# secondary_LTC.net
KiCad netlist of a schematic drawn in Altium Designer
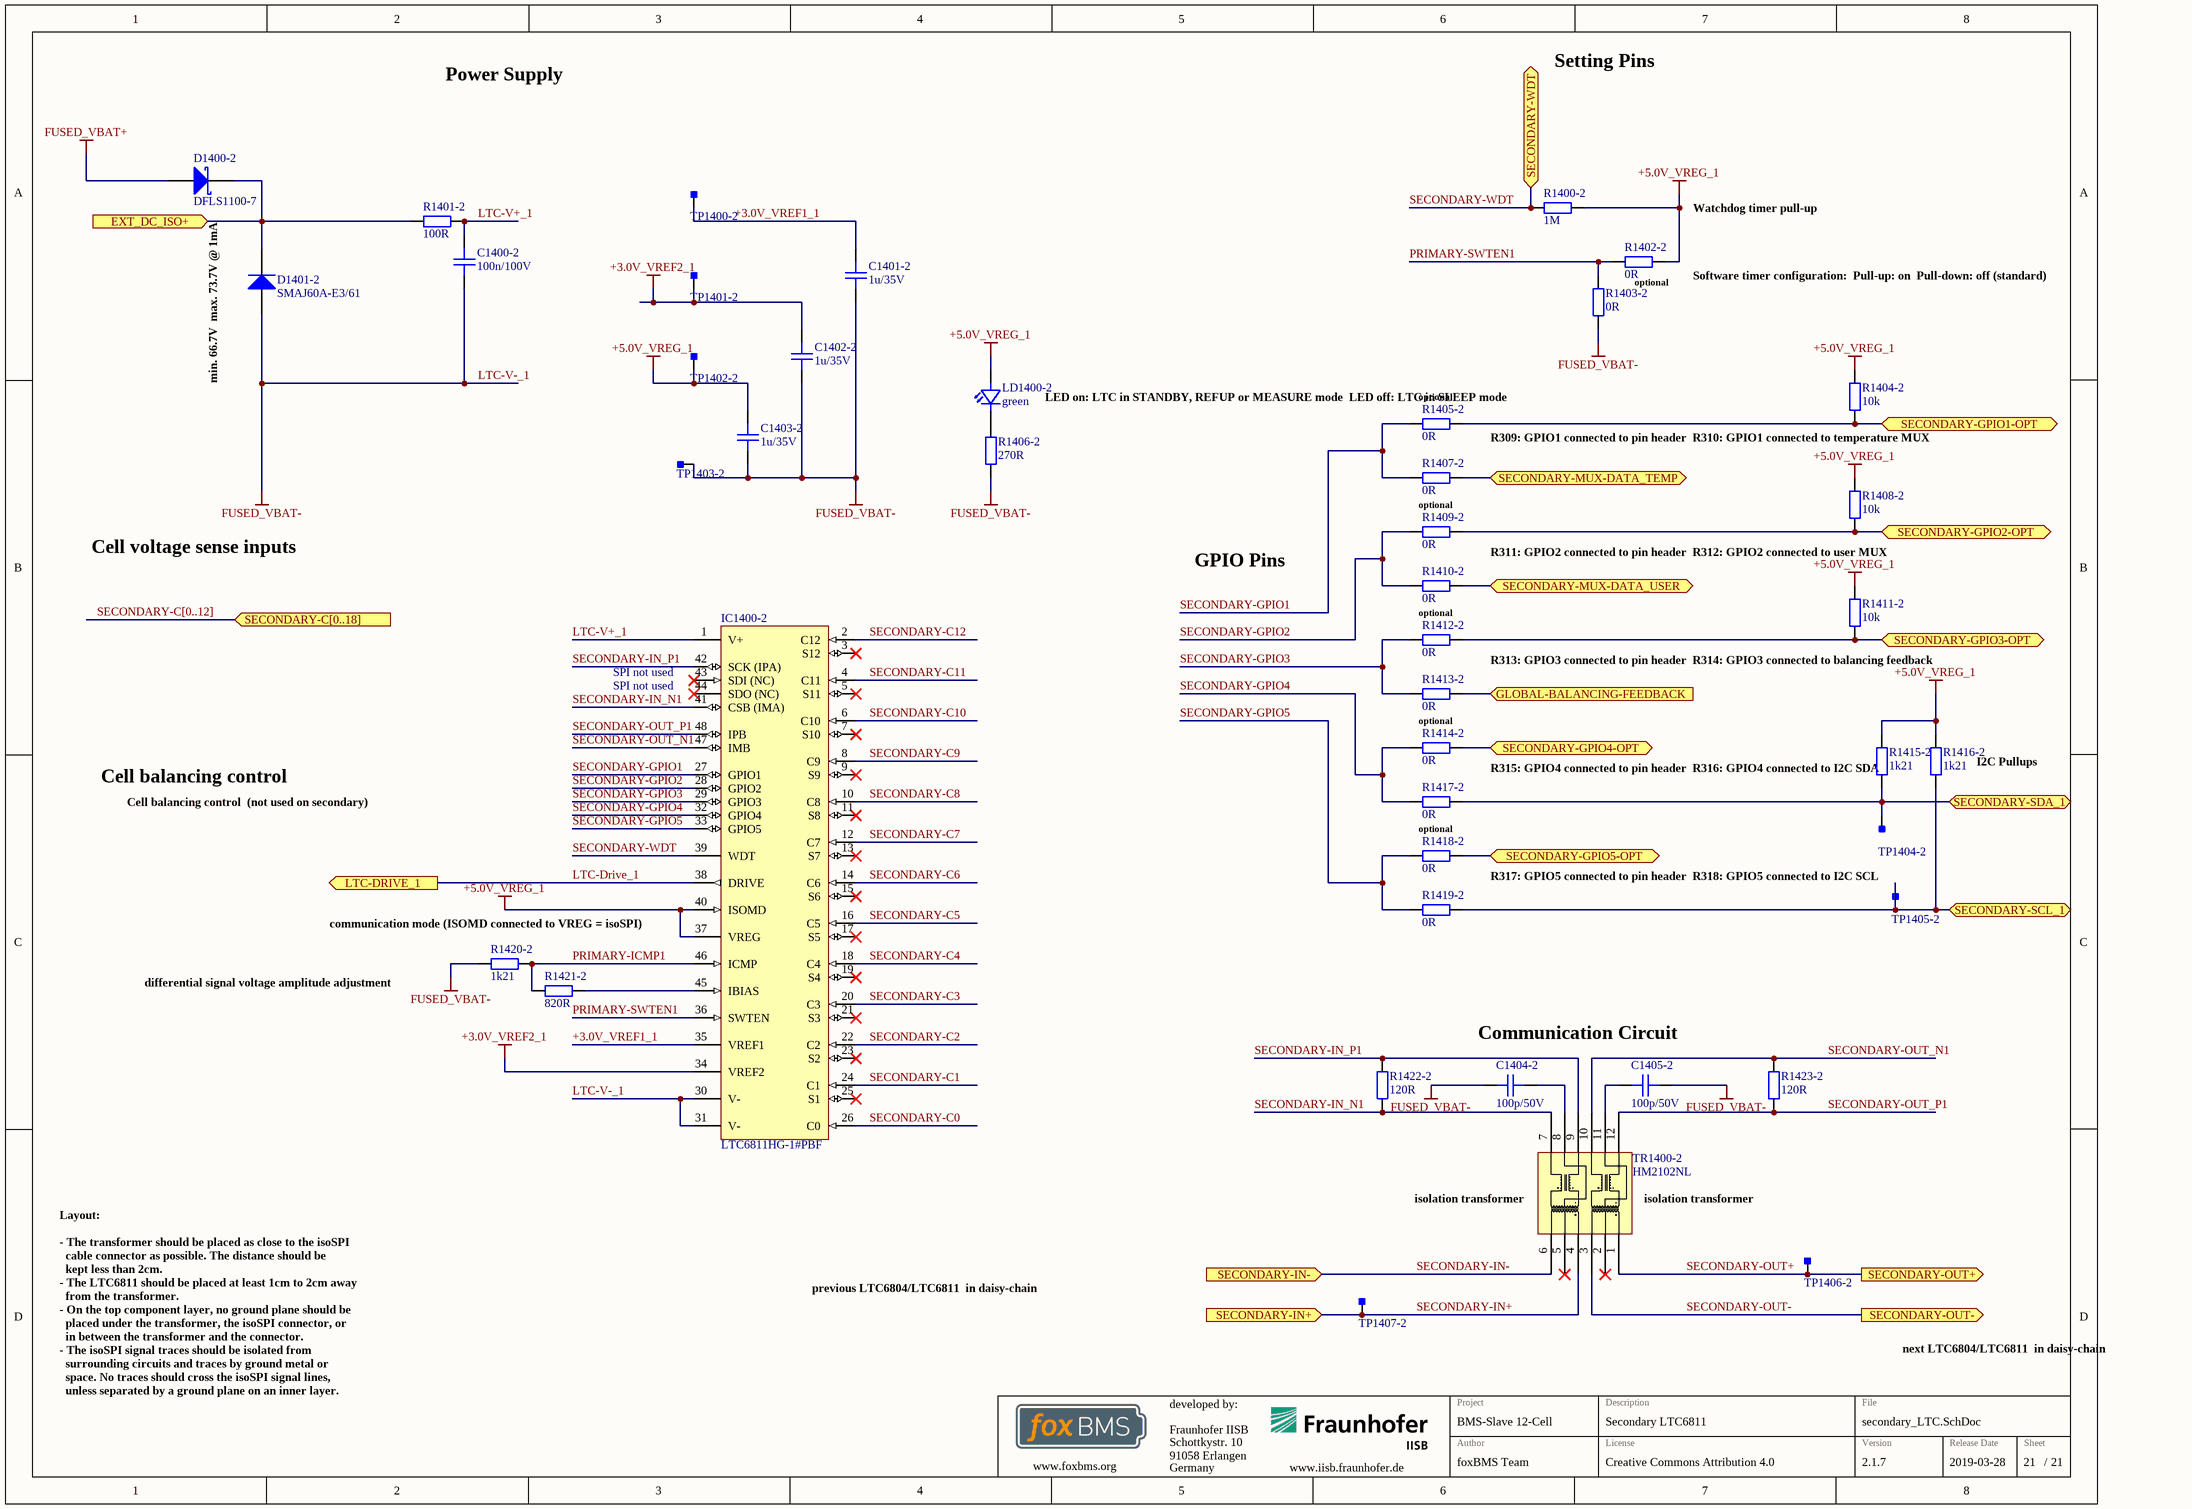
[diagram p0: secondary_LTC.SchDoc]

(export (version "E")
  (design (tool "Eeschema 10.0.6"))
  (components
    (comp (ref "C1400-2")
      (value "100n/100V")
      (footprint "CAPC2012X14N")
      (description "MLCC")
      (fields (field (name "PART NUMBER") "gen_C_ceramic_100n_100V_X7R_0805"))
      (libsource (lib "OE750") (part "C"))
    )
    (comp (ref "C1401-2")
      (value "1u/35V")
      (footprint "CAPC1608X08N")
      (description "MLCC")
      (fields (field (name "PART NUMBER") "gen_C_ceramic_1u_35V_X7R_0603"))
      (libsource (lib "OE750") (part "C"))
    )
    (comp (ref "C1402-2")
      (value "1u/35V")
      (footprint "CAPC1608X08N")
      (description "MLCC")
      (fields (field (name "PART NUMBER") "gen_C_ceramic_1u_35V_X7R_0603"))
      (libsource (lib "OE750") (part "C"))
    )
    (comp (ref "C1403-2")
      (value "1u/35V")
      (footprint "CAPC1608X08N")
      (description "MLCC")
      (fields (field (name "PART NUMBER") "gen_C_ceramic_1u_35V_X7R_0603"))
      (libsource (lib "OE750") (part "C"))
    )
    (comp (ref "C1404-2")
      (value "100p/50V")
      (footprint "CAPC1608X08N")
      (description "MLCC")
      (fields (field (name "PART NUMBER") "gen_C_ceramic_100p_50V_C0G_0603"))
      (libsource (lib "OE750") (part "C"))
    )
    (comp (ref "C1405-2")
      (value "100p/50V")
      (footprint "CAPC1608X08N")
      (description "MLCC")
      (fields (field (name "PART NUMBER") "gen_C_ceramic_100p_50V_C0G_0603"))
      (libsource (lib "OE750") (part "C"))
    )
    (comp (ref "D1400-2")
      (value "DFLS1100-7")
      (footprint "DIOD-POWERDI123-2_V")
      (fields (field (name "MANUFACTURER") "Diodes Inc"))
      (libsource (lib "Altium Content Vault") (part "DSKY-AK-2"))
    )
    (comp (ref "D1401-2")
      (value "SMAJ60A-E3/61")
      (footprint "VISH-DO-214AC-2_N")
      (fields (field (name "MANUFACTURER") "Vishay Semiconductor"))
      (libsource (lib "Altium Content Vault") (part "VISH-K1A2-2"))
    )
    (comp (ref "IC1400-2")
      (value "LTC6811HG-1#PBF")
      (footprint "LT-G-48_L")
      (description "Multicell Battery Monitor, 60 V Vin MAX, 48-pin SOP (G-48), -40 to 125 degC, Pb-Free")
      (fields (field (name "MANUFACTURER") "Linear Technology"))
      (libsource (lib "OE750") (part "LTC6811HG-1#PBF"))
    )
    (comp (ref "LD1400-2")
      (value "green")
      (footprint "LEDC1608X07N")
      (description "LED")
      (fields (field (name "PART NUMBER") "gen_LED_0603_green"))
      (libsource (lib "OE750") (part "D_LED"))
    )
    (comp (ref "R1400-2")
      (value "1M")
      (footprint "RESC1608X05N")
      (description "SMD Resistor 1M 0603")
      (fields (field (name "PART NUMBER") "gen_R_1M_0603") (field (name "TOLERANCE") "1%"))
      (libsource (lib "OE750") (part "R"))
    )
    (comp (ref "R1401-2")
      (value "100R")
      (footprint "RESC2012X05N")
      (description "SMD Resistor 100R 0805")
      (fields (field (name "PART NUMBER") "gen_R_100R_0805") (field (name "TOLERANCE") "1%"))
      (libsource (lib "OE750") (part "R"))
    )
    (comp (ref "R1402-2")
      (value "0R")
      (footprint "RESC1608X05N")
      (description "SMD Resistor 0R 0603")
      (fields (field (name "PART NUMBER") "gen_R_0R_0603") (field (name "POWER") "0.1W"))
      (libsource (lib "OE750") (part "R"))
    )
    (comp (ref "R1403-2")
      (value "0R")
      (footprint "RESC1608X05N")
      (description "SMD Resistor 0R 0603")
      (fields (field (name "PART NUMBER") "gen_R_0R_0603") (field (name "POWER") "0.1W"))
      (libsource (lib "OE750") (part "R"))
    )
    (comp (ref "R1404-2")
      (value "10k")
      (footprint "RESC1608X05N")
      (description "SMD Resistor 10k 0603")
      (fields (field (name "PART NUMBER") "gen_R_10k_0603") (field (name "TOLERANCE") "1%"))
      (libsource (lib "OE750") (part "R"))
    )
    (comp (ref "R1405-2")
      (value "0R")
      (footprint "RESC1608X05N")
      (description "SMD Resistor 0R 0603")
      (fields (field (name "PART NUMBER") "gen_R_0R_0603") (field (name "POWER") "0.1W"))
      (libsource (lib "OE750") (part "R"))
    )
    (comp (ref "R1406-2")
      (value "270R")
      (footprint "RESC1608X05N")
      (description "SMD Resistor 270R 0603")
      (fields (field (name "PART NUMBER") "gen_R_270R_0603") (field (name "TOLERANCE") "1%"))
      (libsource (lib "OE750") (part "R"))
    )
    (comp (ref "R1407-2")
      (value "0R")
      (footprint "RESC1608X05N")
      (description "SMD Resistor 0R 0603")
      (fields (field (name "PART NUMBER") "gen_R_0R_0603") (field (name "POWER") "0.1W"))
      (libsource (lib "OE750") (part "R"))
    )
    (comp (ref "R1408-2")
      (value "10k")
      (footprint "RESC1608X05N")
      (description "SMD Resistor 10k 0603")
      (fields (field (name "PART NUMBER") "gen_R_10k_0603") (field (name "TOLERANCE") "1%"))
      (libsource (lib "OE750") (part "R"))
    )
    (comp (ref "R1409-2")
      (value "0R")
      (footprint "RESC1608X05N")
      (description "SMD Resistor 0R 0603")
      (fields (field (name "PART NUMBER") "gen_R_0R_0603") (field (name "POWER") "0.1W"))
      (libsource (lib "OE750") (part "R"))
    )
    (comp (ref "R1410-2")
      (value "0R")
      (footprint "RESC1608X05N")
      (description "SMD Resistor 0R 0603")
      (fields (field (name "PART NUMBER") "gen_R_0R_0603") (field (name "POWER") "0.1W"))
      (libsource (lib "OE750") (part "R"))
    )
    (comp (ref "R1411-2")
      (value "10k")
      (footprint "RESC1608X05N")
      (description "SMD Resistor 10k 0603")
      (fields (field (name "PART NUMBER") "gen_R_10k_0603") (field (name "TOLERANCE") "1%"))
      (libsource (lib "OE750") (part "R"))
    )
    (comp (ref "R1412-2")
      (value "0R")
      (footprint "RESC1608X05N")
      (description "SMD Resistor 0R 0603")
      (fields (field (name "PART NUMBER") "gen_R_0R_0603") (field (name "POWER") "0.1W"))
      (libsource (lib "OE750") (part "R"))
    )
    (comp (ref "R1413-2")
      (value "0R")
      (footprint "RESC1608X05N")
      (description "SMD Resistor 0R 0603")
      (fields (field (name "PART NUMBER") "gen_R_0R_0603") (field (name "POWER") "0.1W"))
      (libsource (lib "OE750") (part "R"))
    )
    (comp (ref "R1414-2")
      (value "0R")
      (footprint "RESC1608X05N")
      (description "SMD Resistor 0R 0603")
      (fields (field (name "PART NUMBER") "gen_R_0R_0603") (field (name "POWER") "0.1W"))
      (libsource (lib "OE750") (part "R"))
    )
    (comp (ref "R1415-2")
      (value "1k21")
      (footprint "RESC1608X05N")
      (description "SMD Resistor 1k21 0603")
      (fields (field (name "PART NUMBER") "gen_R_1k21_0603") (field (name "TOLERANCE") "1%"))
      (libsource (lib "OE750") (part "R"))
    )
    (comp (ref "R1416-2")
      (value "1k21")
      (footprint "RESC1608X05N")
      (description "SMD Resistor 1k21 0603")
      (fields (field (name "PART NUMBER") "gen_R_1k21_0603") (field (name "TOLERANCE") "1%"))
      (libsource (lib "OE750") (part "R"))
    )
    (comp (ref "R1417-2")
      (value "0R")
      (footprint "RESC1608X05N")
      (description "SMD Resistor 0R 0603")
      (fields (field (name "PART NUMBER") "gen_R_0R_0603") (field (name "POWER") "0.1W"))
      (libsource (lib "OE750") (part "R"))
    )
    (comp (ref "R1418-2")
      (value "0R")
      (footprint "RESC1608X05N")
      (description "SMD Resistor 0R 0603")
      (fields (field (name "PART NUMBER") "gen_R_0R_0603") (field (name "POWER") "0.1W"))
      (libsource (lib "OE750") (part "R"))
    )
    (comp (ref "R1419-2")
      (value "0R")
      (footprint "RESC1608X05N")
      (description "SMD Resistor 0R 0603")
      (fields (field (name "PART NUMBER") "gen_R_0R_0603") (field (name "POWER") "0.1W"))
      (libsource (lib "OE750") (part "R"))
    )
    (comp (ref "R1420-2")
      (value "1k21")
      (footprint "RESC1608X05N")
      (description "SMD Resistor 1k21 0603")
      (fields (field (name "PART NUMBER") "gen_R_1k21_0603") (field (name "TOLERANCE") "1%"))
      (libsource (lib "OE750") (part "R"))
    )
    (comp (ref "R1421-2")
      (value "820R")
      (footprint "RESC1608X05N")
      (description "SMD Resistor 820R 0603")
      (fields (field (name "PART NUMBER") "gen_R_820R_0603") (field (name "TOLERANCE") "1%"))
      (libsource (lib "OE750") (part "R"))
    )
    (comp (ref "R1422-2")
      (value "120R")
      (footprint "RESC1608X05N")
      (description "SMD Resistor 120R 0603")
      (fields (field (name "PART NUMBER") "gen_R_120R_0603") (field (name "TOLERANCE") "1%"))
      (libsource (lib "OE750") (part "R"))
    )
    (comp (ref "R1423-2")
      (value "120R")
      (footprint "RESC1608X05N")
      (description "SMD Resistor 120R 0603")
      (fields (field (name "PART NUMBER") "gen_R_120R_0603") (field (name "TOLERANCE") "1%"))
      (libsource (lib "OE750") (part "R"))
    )
    (comp (ref "TP1400-2")
      (value "Testpoint_Square")
      (footprint "Testpoint_S1")
      (description "Testpoint, square")
      (libsource (lib "OE750") (part "Testpoint_Square"))
    )
    (comp (ref "TP1401-2")
      (value "Testpoint_Square")
      (footprint "Testpoint_S1")
      (description "Testpoint, square")
      (libsource (lib "OE750") (part "Testpoint_Square"))
    )
    (comp (ref "TP1402-2")
      (value "Testpoint_Square")
      (footprint "Testpoint_S1")
      (description "Testpoint, square")
      (libsource (lib "OE750") (part "Testpoint_Square"))
    )
    (comp (ref "TP1403-2")
      (value "Testpoint_Square")
      (footprint "Testpoint_S1")
      (description "Testpoint, square")
      (libsource (lib "OE750") (part "Testpoint_Square"))
    )
    (comp (ref "TP1404-2")
      (value "Testpoint_Square")
      (footprint "Testpoint_S1")
      (description "Testpoint, square")
      (libsource (lib "OE750") (part "Testpoint_Square"))
    )
    (comp (ref "TP1405-2")
      (value "Testpoint_Square")
      (footprint "Testpoint_S1")
      (description "Testpoint, square")
      (libsource (lib "OE750") (part "Testpoint_Square"))
    )
    (comp (ref "TP1406-2")
      (value "Testpoint_Square")
      (footprint "Testpoint_S1")
      (description "Testpoint, square")
      (libsource (lib "OE750") (part "Testpoint_Square"))
    )
    (comp (ref "TP1407-2")
      (value "Testpoint_Square")
      (footprint "Testpoint_S1")
      (description "Testpoint, square")
      (libsource (lib "OE750") (part "Testpoint_Square"))
    )
    (comp (ref "TR1400-2")
      (value "HM2102NL")
      (footprint "HM2102NL")
      (description "Pulse HM2102NL BMS Transformer")
      (fields (field (name "MANUFACTURER") "Pulse"))
      (libsource (lib "OE750") (part "HM2102NL"))
    )
  )
  (nets
    (net (code "1") (name "+3.0V_VREF2_1") (class "Default")
      (node (ref "C1402-2") (pin "2") (pinfunction "2_2") (pintype "passive"))
      (node (ref "IC1400-2") (pin "34") (pinfunction "VREF2_34") (pintype "passive"))
      (node (ref "TP1401-2") (pin "1") (pinfunction "1_1") (pintype "passive"))
    )
    (net (code "2") (name "+5.0V_VREG_1") (class "Default")
      (node (ref "C1403-2") (pin "2") (pinfunction "2_2") (pintype "passive"))
      (node (ref "IC1400-2") (pin "37") (pinfunction "VREG_37") (pintype "power_in"))
      (node (ref "IC1400-2") (pin "40") (pinfunction "ISOMD_40") (pintype "input"))
      (node (ref "LD1400-2") (pin "2") (pinfunction "A_2") (pintype "passive"))
      (node (ref "R1400-2") (pin "2") (pinfunction "2_2") (pintype "passive"))
      (node (ref "R1402-2") (pin "2") (pinfunction "2_2") (pintype "passive"))
      (node (ref "R1404-2") (pin "2") (pinfunction "2_2") (pintype "passive"))
      (node (ref "R1408-2") (pin "2") (pinfunction "2_2") (pintype "passive"))
      (node (ref "R1411-2") (pin "2") (pinfunction "2_2") (pintype "passive"))
      (node (ref "R1415-2") (pin "2") (pinfunction "2_2") (pintype "passive"))
      (node (ref "R1416-2") (pin "2") (pinfunction "2_2") (pintype "passive"))
      (node (ref "TP1402-2") (pin "1") (pinfunction "1_1") (pintype "passive"))
    )
    (net (code "3") (name "/+3.0V_VREF1_1") (class "Default")
      (node (ref "C1401-2") (pin "2") (pinfunction "2_2") (pintype "passive"))
      (node (ref "IC1400-2") (pin "35") (pinfunction "VREF1_35") (pintype "passive"))
      (node (ref "TP1400-2") (pin "1") (pinfunction "1_1") (pintype "passive"))
    )
    (net (code "4") (name "/EXT_DC_ISO+") (class "Default")
      (node (ref "D1400-2") (pin "2") (pinfunction "K_2") (pintype "passive"))
      (node (ref "D1401-2") (pin "1") (pinfunction "K_1") (pintype "passive"))
      (node (ref "R1401-2") (pin "1") (pinfunction "1_1") (pintype "passive"))
    )
    (net (code "5") (name "/GLOBAL-BALANCING-FEEDBACK") (class "Default")
      (node (ref "R1413-2") (pin "1") (pinfunction "1_1") (pintype "passive"))
    )
    (net (code "6") (name "/LTC-Drive_1") (class "Default")
      (node (ref "IC1400-2") (pin "38") (pinfunction "DRIVE_38") (pintype "output"))
    )
    (net (code "7") (name "/LTC-V+_1") (class "Default")
      (node (ref "C1400-2") (pin "1") (pinfunction "1_1") (pintype "passive"))
      (node (ref "IC1400-2") (pin "1") (pinfunction "V+_1") (pintype "power_in"))
      (node (ref "R1401-2") (pin "2") (pinfunction "2_2") (pintype "passive"))
    )
    (net (code "8") (name "/PRIMARY-ICMP1") (class "Default")
      (node (ref "IC1400-2") (pin "46") (pinfunction "ICMP_46") (pintype "input"))
      (node (ref "R1420-2") (pin "2") (pinfunction "2_2") (pintype "passive"))
      (node (ref "R1421-2") (pin "1") (pinfunction "1_1") (pintype "passive"))
    )
    (net (code "9") (name "/PRIMARY-SWTEN1") (class "Default")
      (node (ref "IC1400-2") (pin "36") (pinfunction "SWTEN_36") (pintype "input"))
      (node (ref "R1402-2") (pin "1") (pinfunction "1_1") (pintype "passive"))
      (node (ref "R1403-2") (pin "2") (pinfunction "2_2") (pintype "passive"))
    )
    (net (code "10") (name "/SECONDARY-C0") (class "Default")
      (node (ref "IC1400-2") (pin "26") (pinfunction "C0_26") (pintype "input"))
    )
    (net (code "11") (name "/SECONDARY-C1") (class "Default")
      (node (ref "IC1400-2") (pin "24") (pinfunction "C1_24") (pintype "input"))
    )
    (net (code "12") (name "/SECONDARY-C2") (class "Default")
      (node (ref "IC1400-2") (pin "22") (pinfunction "C2_22") (pintype "input"))
    )
    (net (code "13") (name "/SECONDARY-C3") (class "Default")
      (node (ref "IC1400-2") (pin "20") (pinfunction "C3_20") (pintype "input"))
    )
    (net (code "14") (name "/SECONDARY-C4") (class "Default")
      (node (ref "IC1400-2") (pin "18") (pinfunction "C4_18") (pintype "input"))
    )
    (net (code "15") (name "/SECONDARY-C5") (class "Default")
      (node (ref "IC1400-2") (pin "16") (pinfunction "C5_16") (pintype "input"))
    )
    (net (code "16") (name "/SECONDARY-C6") (class "Default")
      (node (ref "IC1400-2") (pin "14") (pinfunction "C6_14") (pintype "input"))
    )
    (net (code "17") (name "/SECONDARY-C7") (class "Default")
      (node (ref "IC1400-2") (pin "12") (pinfunction "C7_12") (pintype "input"))
    )
    (net (code "18") (name "/SECONDARY-C8") (class "Default")
      (node (ref "IC1400-2") (pin "10") (pinfunction "C8_10") (pintype "input"))
    )
    (net (code "19") (name "/SECONDARY-C9") (class "Default")
      (node (ref "IC1400-2") (pin "8") (pinfunction "C9_8") (pintype "input"))
    )
    (net (code "20") (name "/SECONDARY-C10") (class "Default")
      (node (ref "IC1400-2") (pin "6") (pinfunction "C10_6") (pintype "input"))
    )
    (net (code "21") (name "/SECONDARY-C11") (class "Default")
      (node (ref "IC1400-2") (pin "4") (pinfunction "C11_4") (pintype "input"))
    )
    (net (code "22") (name "/SECONDARY-C12") (class "Default")
      (node (ref "IC1400-2") (pin "2") (pinfunction "C12_2") (pintype "input"))
    )
    (net (code "24") (name "/SECONDARY-GPIO1") (class "Default")
      (node (ref "IC1400-2") (pin "27") (pinfunction "GPIO1_27") (pintype "bidirectional"))
      (node (ref "R1405-2") (pin "2") (pinfunction "2_2") (pintype "passive"))
      (node (ref "R1407-2") (pin "2") (pinfunction "2_2") (pintype "passive"))
    )
    (net (code "25") (name "/SECONDARY-GPIO1-OPT") (class "Default")
      (node (ref "R1404-2") (pin "1") (pinfunction "1_1") (pintype "passive"))
      (node (ref "R1405-2") (pin "1") (pinfunction "1_1") (pintype "passive"))
    )
    (net (code "26") (name "/SECONDARY-GPIO2") (class "Default")
      (node (ref "IC1400-2") (pin "28") (pinfunction "GPIO2_28") (pintype "bidirectional"))
      (node (ref "R1409-2") (pin "2") (pinfunction "2_2") (pintype "passive"))
      (node (ref "R1410-2") (pin "2") (pinfunction "2_2") (pintype "passive"))
    )
    (net (code "27") (name "/SECONDARY-GPIO2-OPT") (class "Default")
      (node (ref "R1408-2") (pin "1") (pinfunction "1_1") (pintype "passive"))
      (node (ref "R1409-2") (pin "1") (pinfunction "1_1") (pintype "passive"))
    )
    (net (code "28") (name "/SECONDARY-GPIO3") (class "Default")
      (node (ref "IC1400-2") (pin "29") (pinfunction "GPIO3_29") (pintype "bidirectional"))
      (node (ref "R1412-2") (pin "2") (pinfunction "2_2") (pintype "passive"))
      (node (ref "R1413-2") (pin "2") (pinfunction "2_2") (pintype "passive"))
    )
    (net (code "29") (name "/SECONDARY-GPIO3-OPT") (class "Default")
      (node (ref "R1411-2") (pin "1") (pinfunction "1_1") (pintype "passive"))
      (node (ref "R1412-2") (pin "1") (pinfunction "1_1") (pintype "passive"))
    )
    (net (code "30") (name "/SECONDARY-GPIO4") (class "Default")
      (node (ref "IC1400-2") (pin "32") (pinfunction "GPIO4_32") (pintype "bidirectional"))
      (node (ref "R1414-2") (pin "2") (pinfunction "2_2") (pintype "passive"))
      (node (ref "R1417-2") (pin "2") (pinfunction "2_2") (pintype "passive"))
    )
    (net (code "31") (name "/SECONDARY-GPIO4-OPT") (class "Default")
      (node (ref "R1414-2") (pin "1") (pinfunction "1_1") (pintype "passive"))
    )
    (net (code "32") (name "/SECONDARY-GPIO5") (class "Default")
      (node (ref "IC1400-2") (pin "33") (pinfunction "GPIO5_33") (pintype "bidirectional"))
      (node (ref "R1418-2") (pin "2") (pinfunction "2_2") (pintype "passive"))
      (node (ref "R1419-2") (pin "2") (pinfunction "2_2") (pintype "passive"))
    )
    (net (code "33") (name "/SECONDARY-GPIO5-OPT") (class "Default")
      (node (ref "R1418-2") (pin "1") (pinfunction "1_1") (pintype "passive"))
    )
    (net (code "34") (name "/SECONDARY-IN+") (class "Default")
      (node (ref "TP1407-2") (pin "1") (pinfunction "1_1") (pintype "passive"))
      (node (ref "TR1400-2") (pin "4") (pintype "passive"))
    )
    (net (code "35") (name "/SECONDARY-IN-") (class "Default")
      (node (ref "TR1400-2") (pin "6") (pintype "passive"))
    )
    (net (code "36") (name "/SECONDARY-IN_N1") (class "Default")
      (node (ref "IC1400-2") (pin "41") (pinfunction "CSB_(IMA)_41") (pintype "bidirectional"))
      (node (ref "R1422-2") (pin "2") (pinfunction "2_2") (pintype "passive"))
      (node (ref "TR1400-2") (pin "7") (pintype "passive"))
    )
    (net (code "37") (name "/SECONDARY-IN_P1") (class "Default")
      (node (ref "IC1400-2") (pin "42") (pinfunction "SCK_(IPA)_42") (pintype "bidirectional"))
      (node (ref "R1422-2") (pin "1") (pinfunction "1_1") (pintype "passive"))
      (node (ref "TR1400-2") (pin "9") (pintype "passive"))
    )
    (net (code "38") (name "/SECONDARY-MUX-DATA_TEMP") (class "Default")
      (node (ref "R1407-2") (pin "1") (pinfunction "1_1") (pintype "passive"))
    )
    (net (code "39") (name "/SECONDARY-MUX-DATA_USER") (class "Default")
      (node (ref "R1410-2") (pin "1") (pinfunction "1_1") (pintype "passive"))
    )
    (net (code "40") (name "/SECONDARY-OUT+") (class "Default")
      (node (ref "TP1406-2") (pin "1") (pinfunction "1_1") (pintype "passive"))
      (node (ref "TR1400-2") (pin "1") (pintype "passive"))
    )
    (net (code "41") (name "/SECONDARY-OUT-") (class "Default")
      (node (ref "TR1400-2") (pin "3") (pintype "passive"))
    )
    (net (code "42") (name "/SECONDARY-OUT_N1") (class "Default")
      (node (ref "IC1400-2") (pin "47") (pinfunction "IMB_47") (pintype "bidirectional"))
      (node (ref "R1423-2") (pin "2") (pinfunction "2_2") (pintype "passive"))
      (node (ref "TR1400-2") (pin "10") (pintype "passive"))
    )
    (net (code "43") (name "/SECONDARY-OUT_P1") (class "Default")
      (node (ref "IC1400-2") (pin "48") (pinfunction "IPB_48") (pintype "bidirectional"))
      (node (ref "R1423-2") (pin "1") (pinfunction "1_1") (pintype "passive"))
      (node (ref "TR1400-2") (pin "12") (pintype "passive"))
    )
    (net (code "44") (name "/SECONDARY-SCL_1") (class "Default")
      (node (ref "R1416-2") (pin "1") (pinfunction "1_1") (pintype "passive"))
      (node (ref "R1419-2") (pin "1") (pinfunction "1_1") (pintype "passive"))
      (node (ref "TP1405-2") (pin "1") (pinfunction "1_1") (pintype "passive"))
    )
    (net (code "45") (name "/SECONDARY-SDA_1") (class "Default")
      (node (ref "R1415-2") (pin "1") (pinfunction "1_1") (pintype "passive"))
      (node (ref "R1417-2") (pin "1") (pinfunction "1_1") (pintype "passive"))
      (node (ref "TP1404-2") (pin "1") (pinfunction "1_1") (pintype "passive"))
    )
    (net (code "46") (name "/SECONDARY-WDT") (class "Default")
      (node (ref "IC1400-2") (pin "39") (pinfunction "WDT_39") (pintype "tri_state"))
      (node (ref "R1400-2") (pin "1") (pinfunction "1_1") (pintype "passive"))
    )
    (net (code "47") (name "FUSED_VBAT+") (class "Default")
      (node (ref "D1400-2") (pin "1") (pinfunction "A_1") (pintype "passive"))
    )
    (net (code "48") (name "FUSED_VBAT-") (class "Default")
      (node (ref "C1400-2") (pin "2") (pinfunction "2_2") (pintype "passive"))
      (node (ref "C1401-2") (pin "1") (pinfunction "1_1") (pintype "passive"))
      (node (ref "C1402-2") (pin "1") (pinfunction "1_1") (pintype "passive"))
      (node (ref "C1403-2") (pin "1") (pinfunction "1_1") (pintype "passive"))
      (node (ref "C1404-2") (pin "1") (pinfunction "1_1") (pintype "passive"))
      (node (ref "C1405-2") (pin "1") (pinfunction "1_1") (pintype "passive"))
      (node (ref "D1401-2") (pin "2") (pinfunction "A_2") (pintype "passive"))
      (node (ref "IC1400-2") (pin "30") (pinfunction "V-_30") (pintype "power_in"))
      (node (ref "IC1400-2") (pin "31") (pinfunction "V-_31") (pintype "power_in"))
      (node (ref "R1403-2") (pin "1") (pinfunction "1_1") (pintype "passive"))
      (node (ref "R1406-2") (pin "1") (pinfunction "1_1") (pintype "passive"))
      (node (ref "R1420-2") (pin "1") (pinfunction "1_1") (pintype "passive"))
      (node (ref "TP1403-2") (pin "1") (pinfunction "1_1") (pintype "passive"))
    )
    (net (code "49") (name "Net-(C1404-2-Pad2)") (class "Default")
      (node (ref "C1404-2") (pin "2") (pinfunction "2_2") (pintype "passive"))
      (node (ref "TR1400-2") (pin "8") (pintype "passive"))
    )
    (net (code "50") (name "Net-(C1405-2-Pad2)") (class "Default")
      (node (ref "C1405-2") (pin "2") (pinfunction "2_2") (pintype "passive"))
      (node (ref "TR1400-2") (pin "11") (pintype "passive"))
    )
    (net (code "51") (name "Net-(IC1400-2-IBIAS)") (class "Default")
      (node (ref "IC1400-2") (pin "45") (pinfunction "IBIAS_45") (pintype "input"))
      (node (ref "R1421-2") (pin "2") (pinfunction "2_2") (pintype "passive"))
    )
    (net (code "52") (name "Net-(LD1400-2-C)") (class "Default")
      (node (ref "LD1400-2") (pin "1") (pinfunction "C_1") (pintype "passive"))
      (node (ref "R1406-2") (pin "2") (pinfunction "2_2") (pintype "passive"))
    )
    (net (code "53") (name "unconnected-(IC1400-2-S1-Pad25)") (class "Default")
      (node (ref "IC1400-2") (pin "25") (pinfunction "S1_25") (pintype "bidirectional+no_connect"))
    )
    (net (code "54") (name "unconnected-(IC1400-2-S2-Pad23)") (class "Default")
      (node (ref "IC1400-2") (pin "23") (pinfunction "S2_23") (pintype "bidirectional+no_connect"))
    )
    (net (code "55") (name "unconnected-(IC1400-2-S3-Pad21)") (class "Default")
      (node (ref "IC1400-2") (pin "21") (pinfunction "S3_21") (pintype "bidirectional+no_connect"))
    )
    (net (code "56") (name "unconnected-(IC1400-2-S4-Pad19)") (class "Default")
      (node (ref "IC1400-2") (pin "19") (pinfunction "S4_19") (pintype "bidirectional+no_connect"))
    )
    (net (code "57") (name "unconnected-(IC1400-2-S5-Pad17)") (class "Default")
      (node (ref "IC1400-2") (pin "17") (pinfunction "S5_17") (pintype "bidirectional+no_connect"))
    )
    (net (code "58") (name "unconnected-(IC1400-2-S6-Pad15)") (class "Default")
      (node (ref "IC1400-2") (pin "15") (pinfunction "S6_15") (pintype "bidirectional+no_connect"))
    )
    (net (code "59") (name "unconnected-(IC1400-2-S7-Pad13)") (class "Default")
      (node (ref "IC1400-2") (pin "13") (pinfunction "S7_13") (pintype "bidirectional+no_connect"))
    )
    (net (code "60") (name "unconnected-(IC1400-2-S8-Pad11)") (class "Default")
      (node (ref "IC1400-2") (pin "11") (pinfunction "S8_11") (pintype "bidirectional+no_connect"))
    )
    (net (code "61") (name "unconnected-(IC1400-2-S9-Pad9)") (class "Default")
      (node (ref "IC1400-2") (pin "9") (pinfunction "S9_9") (pintype "bidirectional+no_connect"))
    )
    (net (code "62") (name "unconnected-(IC1400-2-S10-Pad7)") (class "Default")
      (node (ref "IC1400-2") (pin "7") (pinfunction "S10_7") (pintype "bidirectional+no_connect"))
    )
    (net (code "63") (name "unconnected-(IC1400-2-S11-Pad5)") (class "Default")
      (node (ref "IC1400-2") (pin "5") (pinfunction "S11_5") (pintype "bidirectional+no_connect"))
    )
    (net (code "64") (name "unconnected-(IC1400-2-S12-Pad3)") (class "Default")
      (node (ref "IC1400-2") (pin "3") (pinfunction "S12_3") (pintype "bidirectional+no_connect"))
    )
    (net (code "65") (name "unconnected-(IC1400-2-SDI_(NC)-Pad43)") (class "Default")
      (node (ref "IC1400-2") (pin "43") (pinfunction "SDI_(NC)_43") (pintype "input+no_connect"))
    )
    (net (code "66") (name "unconnected-(IC1400-2-SDO_(NC)-Pad44)") (class "Default")
      (node (ref "IC1400-2") (pin "44") (pinfunction "SDO_(NC)_44") (pintype "open_collector+no_connect"))
    )
    (net (code "67") (name "unconnected-(TR1400-2-Pad2)") (class "Default")
      (node (ref "TR1400-2") (pin "2") (pintype "passive+no_connect"))
    )
    (net (code "68") (name "unconnected-(TR1400-2-Pad5)") (class "Default")
      (node (ref "TR1400-2") (pin "5") (pintype "passive+no_connect"))
    )
  )
)
